# USB-UART.net
KiCad netlist of a schematic drawn in Altium Designer
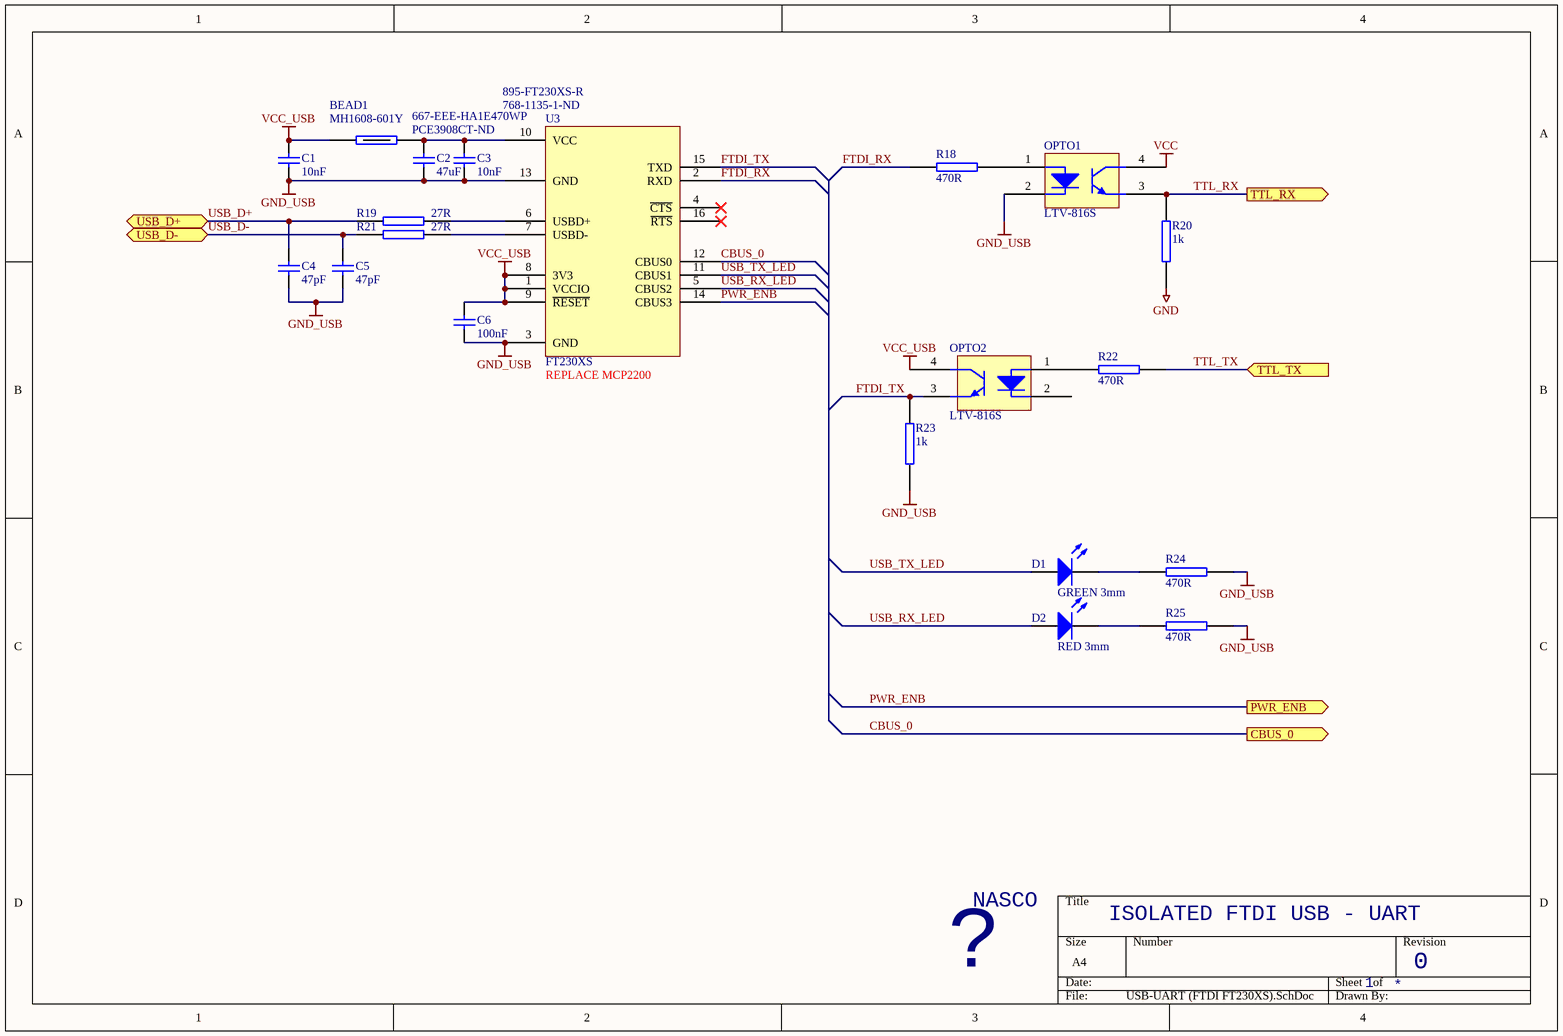
[diagram p0: USB-UART (FTDI FT230XS).SchDoc]

(export (version "E")
  (design (tool "Eeschema 10.0.6"))
  (components
    (comp (ref "BEAD1")
      (value "MH1608-601Y")
      (footprint "RES (3D) - 0603")
      (description "FERRITE BEAD 0603 BOURNS MH1608-601Y")
      (libsource (lib "Schlib1") (part "FERRITE BEAD 0603"))
    )
    (comp (ref "C1")
      (value "10nF")
      (footprint "CAP (3D) - 0603")
      (description "Capacitor")
      (libsource (lib "Miscellaneous Devices") (part "Cap"))
    )
    (comp (ref "C2")
      (value "47uF")
      (footprint "CAP ELECTRO SIZE-D")
      (description "Capacitor")
      (fields
        (field (name "SUPPLIER PART NUMBER 1") "PCE3908CT-ND")
        (field (name "SUPPLIER PART NUMBER 2") "667-EEE-HA1E470WP")
      )
      (libsource (lib "Miscellaneous Devices") (part "Cap"))
    )
    (comp (ref "C3")
      (value "10nF")
      (footprint "CAP (3D) - 0603")
      (description "Capacitor")
      (libsource (lib "Miscellaneous Devices") (part "Cap"))
    )
    (comp (ref "C4")
      (value "47pF")
      (footprint "CAP (3D) - 0603")
      (description "Capacitor")
      (libsource (lib "Miscellaneous Devices") (part "Cap"))
    )
    (comp (ref "C5")
      (value "47pF")
      (footprint "CAP (3D) - 0603")
      (description "Capacitor")
      (libsource (lib "Miscellaneous Devices") (part "Cap"))
    )
    (comp (ref "C6")
      (value "100nF")
      (footprint "CAP (3D) - 0603")
      (description "Capacitor")
      (libsource (lib "Miscellaneous Devices") (part "Cap"))
    )
    (comp (ref "D1")
      (value "GREEN 3mm")
      (footprint "LED(3D) 3MM VERTICAL (GREEN)")
      (description "3mm RED LED")
      (fields (field (name "MOUSER PART NO.") "604-WP132XIT") (field (name "FARNELL PART NO.") "1003393"))
      (libsource (lib "NASCO") (part "LED 3mm RED"))
    )
    (comp (ref "D2")
      (value "RED 3mm")
      (footprint "LED(3D) 3MM VERTICAL (GREEN)")
      (description "3mm RED LED")
      (fields (field (name "MOUSER PART NO.") "604-WP132XIT") (field (name "FARNELL PART NO.") "1003393"))
      (libsource (lib "NASCO") (part "LED 3mm RED"))
    )
    (comp (ref "OPTO1")
      (value "LTV-816S")
      (footprint "S-DIP-B8")
      (description "Transistor Output Optocoupler")
      (libsource (lib "") (part "LTV-816S_1"))
    )
    (comp (ref "OPTO2")
      (value "LTV-816S")
      (footprint "S-DIP-B8")
      (description "Transistor Output Optocoupler")
      (libsource (lib "Schlib1") (part "LTV-816S"))
    )
    (comp (ref "R18")
      (value "470R")
      (footprint "RES (3D) - 0603")
      (description "RESISTOR SMD 0603 1k")
      (libsource (lib "NASCO Resistors") (part "RES SMD 0603 1k"))
    )
    (comp (ref "R19")
      (value "27R")
      (footprint "RES (3D) - 0603")
      (description "RESISTOR SMD 0603")
      (libsource (lib "NASCO Resistors") (part "RES SMD 0603 100R"))
    )
    (comp (ref "R20")
      (value "1k")
      (footprint "RES (3D) - 0603")
      (description "RESISTOR SMD 0603 1k")
      (libsource (lib "NASCO Resistors") (part "RES SMD 0603 1k"))
    )
    (comp (ref "R21")
      (value "27R")
      (footprint "RES (3D) - 0603")
      (description "RESISTOR SMD 0603")
      (libsource (lib "NASCO Resistors") (part "RES SMD 0603 100R"))
    )
    (comp (ref "R22")
      (value "470R")
      (footprint "RES (3D) - 0603")
      (description "RESISTOR SMD 0603 1k")
      (libsource (lib "NASCO Resistors") (part "RES SMD 0603 1k"))
    )
    (comp (ref "R23")
      (value "1k")
      (footprint "RES (3D) - 0603")
      (description "RESISTOR SMD 0603 1k")
      (libsource (lib "NASCO Resistors") (part "RES SMD 0603 1k"))
    )
    (comp (ref "R24")
      (value "470R")
      (footprint "RES (3D) - 0603")
      (description "RESISTOR SMD 0603 1k")
      (libsource (lib "NASCO Resistors") (part "RES SMD 0603 1k"))
    )
    (comp (ref "R25")
      (value "470R")
      (footprint "RES (3D) - 0603")
      (description "RESISTOR SMD 0603 1k")
      (libsource (lib "NASCO Resistors") (part "RES SMD 0603 1k"))
    )
    (comp (ref "U3")
      (value "FT230XS")
      (footprint "SSOP16_L")
      (description "FTDI FT230XS USB - UART")
      (fields
        (field (name "SUPPLIER PART NUMBER 1") "768-1135-1-ND")
        (field (name "SUPPLIER PART NUMBER 2") "895-FT230XS-R")
      )
      (libsource (lib "Schlib1") (part "FTDI FT230XS"))
    )
  )
  (nets
    (net (code "1") (name "/CBUS_0") (class "Default")
      (node (ref "U3") (pin "12") (pinfunction "CBUS0_12") (pintype "passive"))
    )
    (net (code "2") (name "/FTDI_RX") (class "Default")
      (node (ref "R18") (pin "1") (pinfunction "1_1") (pintype "passive"))
      (node (ref "U3") (pin "2") (pinfunction "RXD_2") (pintype "passive"))
    )
    (net (code "3") (name "/FTDI_TX") (class "Default")
      (node (ref "OPTO2") (pin "3") (pinfunction "3_3") (pintype "passive"))
      (node (ref "R23") (pin "2") (pinfunction "2_2") (pintype "passive"))
      (node (ref "U3") (pin "15") (pinfunction "TXD_15") (pintype "passive"))
    )
    (net (code "4") (name "/PWR_ENB") (class "Default")
      (node (ref "U3") (pin "14") (pinfunction "CBUS3_14") (pintype "passive"))
    )
    (net (code "5") (name "/TTL_RX") (class "Default")
      (node (ref "OPTO1") (pin "3") (pinfunction "3_3") (pintype "passive"))
      (node (ref "R20") (pin "2") (pinfunction "2_2") (pintype "passive"))
    )
    (net (code "6") (name "/TTL_TX") (class "Default")
      (node (ref "R22") (pin "2") (pinfunction "2_2") (pintype "passive"))
    )
    (net (code "7") (name "/USB_D+") (class "Default")
      (node (ref "C4") (pin "2") (pinfunction "2_2") (pintype "passive"))
      (node (ref "R19") (pin "1") (pinfunction "1_1") (pintype "passive"))
    )
    (net (code "8") (name "/USB_D-") (class "Default")
      (node (ref "C5") (pin "2") (pinfunction "2_2") (pintype "passive"))
      (node (ref "R21") (pin "1") (pinfunction "1_1") (pintype "passive"))
    )
    (net (code "9") (name "/USB_RX_LED") (class "Default")
      (node (ref "D2") (pin "1") (pinfunction "A_1") (pintype "passive"))
      (node (ref "U3") (pin "5") (pinfunction "CBUS2_5") (pintype "passive"))
    )
    (net (code "10") (name "/USB_TX_LED") (class "Default")
      (node (ref "D1") (pin "1") (pinfunction "A_1") (pintype "passive"))
      (node (ref "U3") (pin "11") (pinfunction "CBUS1_11") (pintype "passive"))
    )
    (net (code "11") (name "GND") (class "Default")
      (node (ref "R20") (pin "1") (pinfunction "1_1") (pintype "passive"))
    )
    (net (code "12") (name "GND_USB") (class "Default")
      (node (ref "C1") (pin "1") (pinfunction "1_1") (pintype "passive"))
      (node (ref "C2") (pin "1") (pinfunction "1_1") (pintype "passive"))
      (node (ref "C3") (pin "1") (pinfunction "1_1") (pintype "passive"))
      (node (ref "C4") (pin "1") (pinfunction "1_1") (pintype "passive"))
      (node (ref "C5") (pin "1") (pinfunction "1_1") (pintype "passive"))
      (node (ref "C6") (pin "1") (pinfunction "1_1") (pintype "passive"))
      (node (ref "OPTO1") (pin "2") (pinfunction "2_2") (pintype "passive"))
      (node (ref "R23") (pin "1") (pinfunction "1_1") (pintype "passive"))
      (node (ref "R24") (pin "2") (pinfunction "2_2") (pintype "passive"))
      (node (ref "R25") (pin "2") (pinfunction "2_2") (pintype "passive"))
      (node (ref "U3") (pin "13") (pinfunction "GND_13") (pintype "passive"))
      (node (ref "U3") (pin "3") (pinfunction "GND_3") (pintype "passive"))
    )
    (net (code "13") (name "Net-(D1-K)") (class "Default")
      (node (ref "D1") (pin "2") (pinfunction "K_2") (pintype "passive"))
      (node (ref "R24") (pin "1") (pinfunction "1_1") (pintype "passive"))
    )
    (net (code "14") (name "Net-(D2-K)") (class "Default")
      (node (ref "D2") (pin "2") (pinfunction "K_2") (pintype "passive"))
      (node (ref "R25") (pin "1") (pinfunction "1_1") (pintype "passive"))
    )
    (net (code "15") (name "Net-(OPTO1-Pad1)") (class "Default")
      (node (ref "OPTO1") (pin "1") (pinfunction "1_1") (pintype "passive"))
      (node (ref "R18") (pin "2") (pinfunction "2_2") (pintype "passive"))
    )
    (net (code "16") (name "Net-(OPTO2-Pad1)") (class "Default")
      (node (ref "OPTO2") (pin "1") (pinfunction "1_1") (pintype "passive"))
      (node (ref "R22") (pin "1") (pinfunction "1_1") (pintype "passive"))
    )
    (net (code "17") (name "Net-(U3-USBD+)") (class "Default")
      (node (ref "R19") (pin "2") (pinfunction "2_2") (pintype "passive"))
      (node (ref "U3") (pin "6") (pinfunction "USBD+_6") (pintype "passive"))
    )
    (net (code "18") (name "Net-(U3-USBD-)") (class "Default")
      (node (ref "R21") (pin "2") (pinfunction "2_2") (pintype "passive"))
      (node (ref "U3") (pin "7") (pinfunction "USBD-_7") (pintype "passive"))
    )
    (net (code "19") (name "Net-(U3-VCC)") (class "Default")
      (node (ref "BEAD1") (pin "2") (pinfunction "2_2") (pintype "passive"))
      (node (ref "C2") (pin "2") (pinfunction "2_2") (pintype "passive"))
      (node (ref "C3") (pin "2") (pinfunction "2_2") (pintype "passive"))
      (node (ref "U3") (pin "10") (pinfunction "VCC_10") (pintype "passive"))
    )
    (net (code "20") (name "VCC") (class "Default")
      (node (ref "OPTO1") (pin "4") (pinfunction "4_4") (pintype "passive"))
    )
    (net (code "21") (name "VCC_USB") (class "Default")
      (node (ref "BEAD1") (pin "1") (pinfunction "1_1") (pintype "passive"))
      (node (ref "C1") (pin "2") (pinfunction "2_2") (pintype "passive"))
      (node (ref "C6") (pin "2") (pinfunction "2_2") (pintype "passive"))
      (node (ref "OPTO2") (pin "4") (pinfunction "4_4") (pintype "passive"))
      (node (ref "U3") (pin "1") (pinfunction "VCCIO_1") (pintype "passive"))
      (node (ref "U3") (pin "8") (pinfunction "3V3_8") (pintype "passive"))
      (node (ref "U3") (pin "9") (pinfunction "~{RESET}_9") (pintype "passive"))
    )
    (net (code "22") (name "unconnected-(OPTO2-Pad2)") (class "Default")
      (node (ref "OPTO2") (pin "2") (pinfunction "2_2") (pintype "passive"))
    )
    (net (code "23") (name "unconnected-(U3-~{CTS}-Pad4)") (class "Default")
      (node (ref "U3") (pin "4") (pinfunction "~{CTS}_4") (pintype "passive+no_connect"))
    )
    (net (code "24") (name "unconnected-(U3-~{RTS}-Pad16)") (class "Default")
      (node (ref "U3") (pin "16") (pinfunction "~{RTS}_16") (pintype "passive+no_connect"))
    )
  )
)
